# rev02_6.net
KiCad netlist of a schematic drawn in Altium Designer
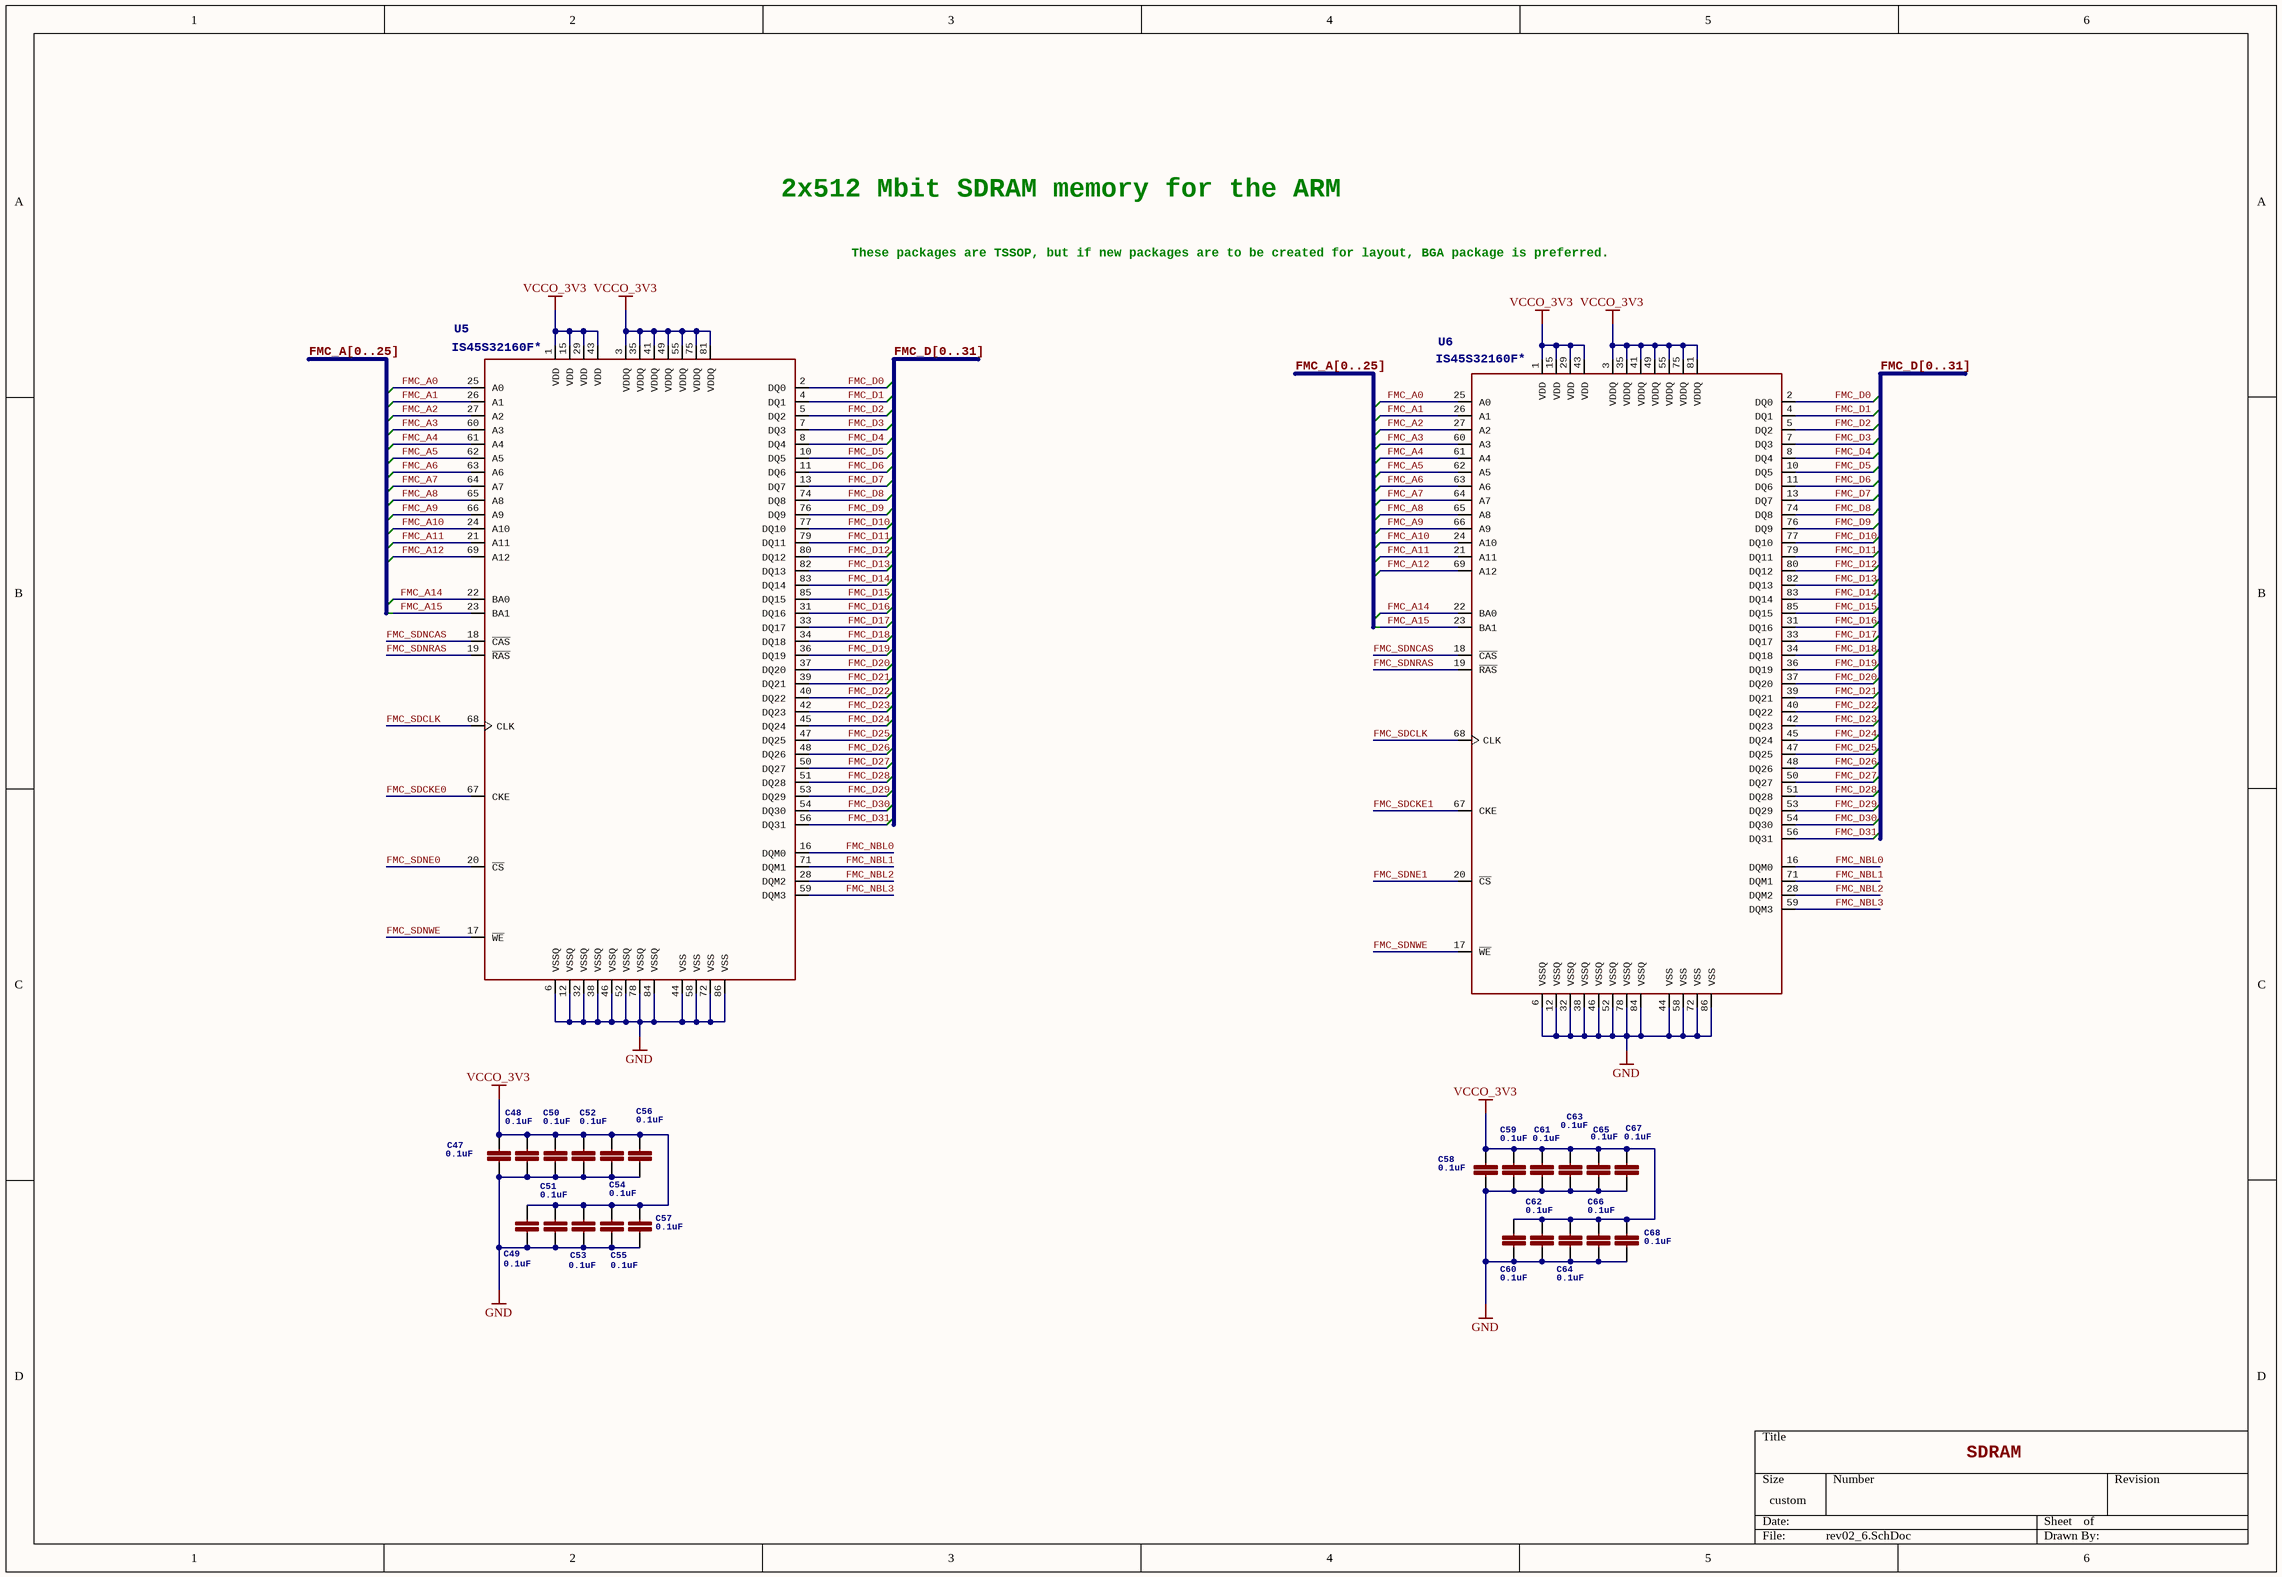
[diagram p0: rev02_6.SchDoc]

(export (version "E")
  (design (tool "Eeschema 10.0.6"))
  (components
    (comp (ref "C47")
      (value "0.1uF")
      (footprint "C_0402")
      (description "0402 CAPACITOR")
      (libsource (lib "resistor") (part "C-EUC0402"))
    )
    (comp (ref "C48")
      (value "0.1uF")
      (footprint "C_0402")
      (description "0402 CAPACITOR")
      (libsource (lib "resistor") (part "C-EUC0402"))
    )
    (comp (ref "C49")
      (value "0.1uF")
      (footprint "C_0402")
      (description "0402 CAPACITOR")
      (libsource (lib "resistor") (part "C-EUC0402"))
    )
    (comp (ref "C50")
      (value "0.1uF")
      (footprint "C_0402")
      (description "0402 CAPACITOR")
      (libsource (lib "resistor") (part "C-EUC0402"))
    )
    (comp (ref "C51")
      (value "0.1uF")
      (footprint "C_0402")
      (description "0402 CAPACITOR")
      (libsource (lib "resistor") (part "C-EUC0402"))
    )
    (comp (ref "C52")
      (value "0.1uF")
      (footprint "C_0402")
      (description "0402 CAPACITOR")
      (libsource (lib "resistor") (part "C-EUC0402"))
    )
    (comp (ref "C53")
      (value "0.1uF")
      (footprint "C_0402")
      (description "0402 CAPACITOR")
      (libsource (lib "resistor") (part "C-EUC0402"))
    )
    (comp (ref "C54")
      (value "0.1uF")
      (footprint "C_0402")
      (description "0402 CAPACITOR")
      (libsource (lib "resistor") (part "C-EUC0402"))
    )
    (comp (ref "C55")
      (value "0.1uF")
      (footprint "C_0402")
      (description "0402 CAPACITOR")
      (libsource (lib "resistor") (part "C-EUC0402"))
    )
    (comp (ref "C56")
      (value "0.1uF")
      (footprint "C_0402")
      (description "0402 CAPACITOR")
      (libsource (lib "resistor") (part "C-EUC0402"))
    )
    (comp (ref "C57")
      (value "0.1uF")
      (footprint "C_0402")
      (description "0402 CAPACITOR")
      (libsource (lib "resistor") (part "C-EUC0402"))
    )
    (comp (ref "C58")
      (value "0.1uF")
      (footprint "C_0402")
      (description "0402 CAPACITOR")
      (libsource (lib "resistor") (part "C-EUC0402"))
    )
    (comp (ref "C59")
      (value "0.1uF")
      (footprint "C_0402")
      (description "0402 CAPACITOR")
      (libsource (lib "resistor") (part "C-EUC0402"))
    )
    (comp (ref "C60")
      (value "0.1uF")
      (footprint "C_0402")
      (description "0402 CAPACITOR")
      (libsource (lib "resistor") (part "C-EUC0402"))
    )
    (comp (ref "C61")
      (value "0.1uF")
      (footprint "C_0402")
      (description "0402 CAPACITOR")
      (libsource (lib "resistor") (part "C-EUC0402"))
    )
    (comp (ref "C62")
      (value "0.1uF")
      (footprint "C_0402")
      (description "0402 CAPACITOR")
      (libsource (lib "resistor") (part "C-EUC0402"))
    )
    (comp (ref "C63")
      (value "0.1uF")
      (footprint "C_0402")
      (description "0402 CAPACITOR")
      (libsource (lib "resistor") (part "C-EUC0402"))
    )
    (comp (ref "C64")
      (value "0.1uF")
      (footprint "C_0402")
      (description "0402 CAPACITOR")
      (libsource (lib "resistor") (part "C-EUC0402"))
    )
    (comp (ref "C65")
      (value "0.1uF")
      (footprint "C_0402")
      (description "0402 CAPACITOR")
      (libsource (lib "resistor") (part "C-EUC0402"))
    )
    (comp (ref "C66")
      (value "0.1uF")
      (footprint "C_0402")
      (description "0402 CAPACITOR")
      (libsource (lib "resistor") (part "C-EUC0402"))
    )
    (comp (ref "C67")
      (value "0.1uF")
      (footprint "C_0402")
      (description "0402 CAPACITOR")
      (libsource (lib "resistor") (part "C-EUC0402"))
    )
    (comp (ref "C68")
      (value "0.1uF")
      (footprint "C_0402")
      (description "0402 CAPACITOR")
      (libsource (lib "resistor") (part "C-EUC0402"))
    )
    (comp (ref "U5")
      (value "IS45S32160F*")
      (footprint "TSSOP50P1180X120-86N")
      (description "16Mx32, 512Mb SDRAM\nClock frequency: 166, 143 MHz")
      (fields (field (name "MPN") "IS45S32160F") (field (name ">NAME") "U5"))
      (libsource (lib "Alpha-IC") (part "IS45S32160F"))
    )
    (comp (ref "U6")
      (value "IS45S32160F*")
      (footprint "TSSOP50P1180X120-86N")
      (description "16Mx32, 512Mb SDRAM\nClock frequency: 166, 143 MHz")
      (fields (field (name "MPN") "IS45S32160F") (field (name ">NAME") "U6"))
      (libsource (lib "Alpha-IC") (part "IS45S32160F"))
    )
  )
  (nets
    (net (code "12") (name "/FMC_A0") (class "Default")
      (node (ref "U5") (pin "25") (pinfunction "A0_25") (pintype "passive"))
      (node (ref "U6") (pin "25") (pinfunction "A0_25") (pintype "passive"))
    )
    (net (code "13") (name "/FMC_A1") (class "Default")
      (node (ref "U5") (pin "26") (pinfunction "A1_26") (pintype "passive"))
      (node (ref "U6") (pin "26") (pinfunction "A1_26") (pintype "passive"))
    )
    (net (code "14") (name "/FMC_A2") (class "Default")
      (node (ref "U5") (pin "27") (pinfunction "A2_27") (pintype "passive"))
      (node (ref "U6") (pin "27") (pinfunction "A2_27") (pintype "passive"))
    )
    (net (code "15") (name "/FMC_A3") (class "Default")
      (node (ref "U5") (pin "60") (pinfunction "A3_60") (pintype "passive"))
      (node (ref "U6") (pin "60") (pinfunction "A3_60") (pintype "passive"))
    )
    (net (code "16") (name "/FMC_A4") (class "Default")
      (node (ref "U5") (pin "61") (pinfunction "A4_61") (pintype "passive"))
      (node (ref "U6") (pin "61") (pinfunction "A4_61") (pintype "passive"))
    )
    (net (code "17") (name "/FMC_A5") (class "Default")
      (node (ref "U5") (pin "62") (pinfunction "A5_62") (pintype "passive"))
      (node (ref "U6") (pin "62") (pinfunction "A5_62") (pintype "passive"))
    )
    (net (code "18") (name "/FMC_A6") (class "Default")
      (node (ref "U5") (pin "63") (pinfunction "A6_63") (pintype "passive"))
      (node (ref "U6") (pin "63") (pinfunction "A6_63") (pintype "passive"))
    )
    (net (code "19") (name "/FMC_A7") (class "Default")
      (node (ref "U5") (pin "64") (pinfunction "A7_64") (pintype "passive"))
      (node (ref "U6") (pin "64") (pinfunction "A7_64") (pintype "passive"))
    )
    (net (code "20") (name "/FMC_A8") (class "Default")
      (node (ref "U5") (pin "65") (pinfunction "A8_65") (pintype "passive"))
      (node (ref "U6") (pin "65") (pinfunction "A8_65") (pintype "passive"))
    )
    (net (code "21") (name "/FMC_A9") (class "Default")
      (node (ref "U5") (pin "66") (pinfunction "A9_66") (pintype "passive"))
      (node (ref "U6") (pin "66") (pinfunction "A9_66") (pintype "passive"))
    )
    (net (code "22") (name "/FMC_A10") (class "Default")
      (node (ref "U5") (pin "24") (pinfunction "A10_24") (pintype "passive"))
      (node (ref "U6") (pin "24") (pinfunction "A10_24") (pintype "passive"))
    )
    (net (code "23") (name "/FMC_A11") (class "Default")
      (node (ref "U5") (pin "21") (pinfunction "A11_21") (pintype "passive"))
      (node (ref "U6") (pin "21") (pinfunction "A11_21") (pintype "passive"))
    )
    (net (code "24") (name "/FMC_A12") (class "Default")
      (node (ref "U5") (pin "69") (pinfunction "A12_69") (pintype "passive"))
      (node (ref "U6") (pin "69") (pinfunction "A12_69") (pintype "passive"))
    )
    (net (code "25") (name "/FMC_A14") (class "Default")
      (node (ref "U5") (pin "22") (pinfunction "BA0_22") (pintype "passive"))
      (node (ref "U6") (pin "22") (pinfunction "BA0_22") (pintype "passive"))
    )
    (net (code "26") (name "/FMC_A15") (class "Default")
      (node (ref "U5") (pin "23") (pinfunction "BA1_23") (pintype "passive"))
      (node (ref "U6") (pin "23") (pinfunction "BA1_23") (pintype "passive"))
    )
    (net (code "28") (name "/FMC_D0") (class "Default")
      (node (ref "U5") (pin "2") (pinfunction "DQ0_2") (pintype "passive"))
      (node (ref "U6") (pin "2") (pinfunction "DQ0_2") (pintype "passive"))
    )
    (net (code "29") (name "/FMC_D1") (class "Default")
      (node (ref "U5") (pin "4") (pinfunction "DQ1_4") (pintype "passive"))
      (node (ref "U6") (pin "4") (pinfunction "DQ1_4") (pintype "passive"))
    )
    (net (code "30") (name "/FMC_D2") (class "Default")
      (node (ref "U5") (pin "5") (pinfunction "DQ2_5") (pintype "passive"))
      (node (ref "U6") (pin "5") (pinfunction "DQ2_5") (pintype "passive"))
    )
    (net (code "31") (name "/FMC_D3") (class "Default")
      (node (ref "U5") (pin "7") (pinfunction "DQ3_7") (pintype "passive"))
      (node (ref "U6") (pin "7") (pinfunction "DQ3_7") (pintype "passive"))
    )
    (net (code "32") (name "/FMC_D4") (class "Default")
      (node (ref "U5") (pin "8") (pinfunction "DQ4_8") (pintype "passive"))
      (node (ref "U6") (pin "8") (pinfunction "DQ4_8") (pintype "passive"))
    )
    (net (code "33") (name "/FMC_D5") (class "Default")
      (node (ref "U5") (pin "10") (pinfunction "DQ5_10") (pintype "passive"))
      (node (ref "U6") (pin "10") (pinfunction "DQ5_10") (pintype "passive"))
    )
    (net (code "34") (name "/FMC_D6") (class "Default")
      (node (ref "U5") (pin "11") (pinfunction "DQ6_11") (pintype "passive"))
      (node (ref "U6") (pin "11") (pinfunction "DQ6_11") (pintype "passive"))
    )
    (net (code "35") (name "/FMC_D7") (class "Default")
      (node (ref "U5") (pin "13") (pinfunction "DQ7_13") (pintype "passive"))
      (node (ref "U6") (pin "13") (pinfunction "DQ7_13") (pintype "passive"))
    )
    (net (code "36") (name "/FMC_D8") (class "Default")
      (node (ref "U5") (pin "74") (pinfunction "DQ8_74") (pintype "passive"))
      (node (ref "U6") (pin "74") (pinfunction "DQ8_74") (pintype "passive"))
    )
    (net (code "37") (name "/FMC_D9") (class "Default")
      (node (ref "U5") (pin "76") (pinfunction "DQ9_76") (pintype "passive"))
      (node (ref "U6") (pin "76") (pinfunction "DQ9_76") (pintype "passive"))
    )
    (net (code "38") (name "/FMC_D10") (class "Default")
      (node (ref "U5") (pin "77") (pinfunction "DQ10_77") (pintype "passive"))
      (node (ref "U6") (pin "77") (pinfunction "DQ10_77") (pintype "passive"))
    )
    (net (code "39") (name "/FMC_D11") (class "Default")
      (node (ref "U5") (pin "79") (pinfunction "DQ11_79") (pintype "passive"))
      (node (ref "U6") (pin "79") (pinfunction "DQ11_79") (pintype "passive"))
    )
    (net (code "40") (name "/FMC_D12") (class "Default")
      (node (ref "U5") (pin "80") (pinfunction "DQ12_80") (pintype "passive"))
      (node (ref "U6") (pin "80") (pinfunction "DQ12_80") (pintype "passive"))
    )
    (net (code "41") (name "/FMC_D13") (class "Default")
      (node (ref "U5") (pin "82") (pinfunction "DQ13_82") (pintype "passive"))
      (node (ref "U6") (pin "82") (pinfunction "DQ13_82") (pintype "passive"))
    )
    (net (code "42") (name "/FMC_D14") (class "Default")
      (node (ref "U5") (pin "83") (pinfunction "DQ14_83") (pintype "passive"))
      (node (ref "U6") (pin "83") (pinfunction "DQ14_83") (pintype "passive"))
    )
    (net (code "43") (name "/FMC_D15") (class "Default")
      (node (ref "U5") (pin "85") (pinfunction "DQ15_85") (pintype "passive"))
      (node (ref "U6") (pin "85") (pinfunction "DQ15_85") (pintype "passive"))
    )
    (net (code "44") (name "/FMC_D16") (class "Default")
      (node (ref "U5") (pin "31") (pinfunction "DQ16_31") (pintype "passive"))
      (node (ref "U6") (pin "31") (pinfunction "DQ16_31") (pintype "passive"))
    )
    (net (code "45") (name "/FMC_D17") (class "Default")
      (node (ref "U5") (pin "33") (pinfunction "DQ17_33") (pintype "passive"))
      (node (ref "U6") (pin "33") (pinfunction "DQ17_33") (pintype "passive"))
    )
    (net (code "46") (name "/FMC_D18") (class "Default")
      (node (ref "U5") (pin "34") (pinfunction "DQ18_34") (pintype "passive"))
      (node (ref "U6") (pin "34") (pinfunction "DQ18_34") (pintype "passive"))
    )
    (net (code "47") (name "/FMC_D19") (class "Default")
      (node (ref "U5") (pin "36") (pinfunction "DQ19_36") (pintype "passive"))
      (node (ref "U6") (pin "36") (pinfunction "DQ19_36") (pintype "passive"))
    )
    (net (code "48") (name "/FMC_D20") (class "Default")
      (node (ref "U5") (pin "37") (pinfunction "DQ20_37") (pintype "passive"))
      (node (ref "U6") (pin "37") (pinfunction "DQ20_37") (pintype "passive"))
    )
    (net (code "49") (name "/FMC_D21") (class "Default")
      (node (ref "U5") (pin "39") (pinfunction "DQ21_39") (pintype "passive"))
      (node (ref "U6") (pin "39") (pinfunction "DQ21_39") (pintype "passive"))
    )
    (net (code "50") (name "/FMC_D22") (class "Default")
      (node (ref "U5") (pin "40") (pinfunction "DQ22_40") (pintype "passive"))
      (node (ref "U6") (pin "40") (pinfunction "DQ22_40") (pintype "passive"))
    )
    (net (code "51") (name "/FMC_D23") (class "Default")
      (node (ref "U5") (pin "42") (pinfunction "DQ23_42") (pintype "passive"))
      (node (ref "U6") (pin "42") (pinfunction "DQ23_42") (pintype "passive"))
    )
    (net (code "52") (name "/FMC_D24") (class "Default")
      (node (ref "U5") (pin "45") (pinfunction "DQ24_45") (pintype "passive"))
      (node (ref "U6") (pin "45") (pinfunction "DQ24_45") (pintype "passive"))
    )
    (net (code "53") (name "/FMC_D25") (class "Default")
      (node (ref "U5") (pin "47") (pinfunction "DQ25_47") (pintype "passive"))
      (node (ref "U6") (pin "47") (pinfunction "DQ25_47") (pintype "passive"))
    )
    (net (code "54") (name "/FMC_D26") (class "Default")
      (node (ref "U5") (pin "48") (pinfunction "DQ26_48") (pintype "passive"))
      (node (ref "U6") (pin "48") (pinfunction "DQ26_48") (pintype "passive"))
    )
    (net (code "55") (name "/FMC_D27") (class "Default")
      (node (ref "U5") (pin "50") (pinfunction "DQ27_50") (pintype "passive"))
      (node (ref "U6") (pin "50") (pinfunction "DQ27_50") (pintype "passive"))
    )
    (net (code "56") (name "/FMC_D28") (class "Default")
      (node (ref "U5") (pin "51") (pinfunction "DQ28_51") (pintype "passive"))
      (node (ref "U6") (pin "51") (pinfunction "DQ28_51") (pintype "passive"))
    )
    (net (code "57") (name "/FMC_D29") (class "Default")
      (node (ref "U5") (pin "53") (pinfunction "DQ29_53") (pintype "passive"))
      (node (ref "U6") (pin "53") (pinfunction "DQ29_53") (pintype "passive"))
    )
    (net (code "58") (name "/FMC_D30") (class "Default")
      (node (ref "U5") (pin "54") (pinfunction "DQ30_54") (pintype "passive"))
      (node (ref "U6") (pin "54") (pinfunction "DQ30_54") (pintype "passive"))
    )
    (net (code "59") (name "/FMC_D31") (class "Default")
      (node (ref "U5") (pin "56") (pinfunction "DQ31_56") (pintype "passive"))
      (node (ref "U6") (pin "56") (pinfunction "DQ31_56") (pintype "passive"))
    )
    (net (code "61") (name "/FMC_NBL0") (class "Default")
      (node (ref "U5") (pin "16") (pinfunction "DQM0_16") (pintype "passive"))
      (node (ref "U6") (pin "16") (pinfunction "DQM0_16") (pintype "passive"))
    )
    (net (code "62") (name "/FMC_NBL1") (class "Default")
      (node (ref "U5") (pin "71") (pinfunction "DQM1_71") (pintype "passive"))
      (node (ref "U6") (pin "71") (pinfunction "DQM1_71") (pintype "passive"))
    )
    (net (code "63") (name "/FMC_NBL2") (class "Default")
      (node (ref "U5") (pin "28") (pinfunction "DQM2_28") (pintype "passive"))
      (node (ref "U6") (pin "28") (pinfunction "DQM2_28") (pintype "passive"))
    )
    (net (code "64") (name "/FMC_NBL3") (class "Default")
      (node (ref "U5") (pin "59") (pinfunction "DQM3_59") (pintype "passive"))
      (node (ref "U6") (pin "59") (pinfunction "DQM3_59") (pintype "passive"))
    )
    (net (code "65") (name "/FMC_SDCKE0") (class "Default")
      (node (ref "U5") (pin "67") (pinfunction "CKE_67") (pintype "passive"))
    )
    (net (code "66") (name "/FMC_SDCKE1") (class "Default")
      (node (ref "U6") (pin "67") (pinfunction "CKE_67") (pintype "passive"))
    )
    (net (code "67") (name "/FMC_SDCLK") (class "Default")
      (node (ref "U5") (pin "68") (pinfunction "CLK_68") (pintype "passive"))
      (node (ref "U6") (pin "68") (pinfunction "CLK_68") (pintype "passive"))
    )
    (net (code "68") (name "/FMC_SDNCAS") (class "Default")
      (node (ref "U5") (pin "18") (pinfunction "~{CAS}_18") (pintype "passive"))
      (node (ref "U6") (pin "18") (pinfunction "~{CAS}_18") (pintype "passive"))
    )
    (net (code "69") (name "/FMC_SDNE0") (class "Default")
      (node (ref "U5") (pin "20") (pinfunction "~{CS}_20") (pintype "passive"))
    )
    (net (code "70") (name "/FMC_SDNE1") (class "Default")
      (node (ref "U6") (pin "20") (pinfunction "~{CS}_20") (pintype "passive"))
    )
    (net (code "71") (name "/FMC_SDNRAS") (class "Default")
      (node (ref "U5") (pin "19") (pinfunction "~{RAS}_19") (pintype "passive"))
      (node (ref "U6") (pin "19") (pinfunction "~{RAS}_19") (pintype "passive"))
    )
    (net (code "72") (name "/FMC_SDNWE") (class "Default")
      (node (ref "U5") (pin "17") (pinfunction "~{WE}_17") (pintype "passive"))
      (node (ref "U6") (pin "17") (pinfunction "~{WE}_17") (pintype "passive"))
    )
    (net (code "73") (name "GND") (class "Default")
      (node (ref "C47") (pin "2") (pinfunction "2_2") (pintype "passive"))
      (node (ref "C48") (pin "2") (pinfunction "2_2") (pintype "passive"))
      (node (ref "C49") (pin "2") (pinfunction "2_2") (pintype "passive"))
      (node (ref "C50") (pin "2") (pinfunction "2_2") (pintype "passive"))
      (node (ref "C51") (pin "2") (pinfunction "2_2") (pintype "passive"))
      (node (ref "C52") (pin "2") (pinfunction "2_2") (pintype "passive"))
      (node (ref "C53") (pin "2") (pinfunction "2_2") (pintype "passive"))
      (node (ref "C54") (pin "2") (pinfunction "2_2") (pintype "passive"))
      (node (ref "C55") (pin "2") (pinfunction "2_2") (pintype "passive"))
      (node (ref "C56") (pin "2") (pinfunction "2_2") (pintype "passive"))
      (node (ref "C57") (pin "2") (pinfunction "2_2") (pintype "passive"))
      (node (ref "C58") (pin "2") (pinfunction "2_2") (pintype "passive"))
      (node (ref "C59") (pin "2") (pinfunction "2_2") (pintype "passive"))
      (node (ref "C60") (pin "2") (pinfunction "2_2") (pintype "passive"))
      (node (ref "C61") (pin "2") (pinfunction "2_2") (pintype "passive"))
      (node (ref "C62") (pin "2") (pinfunction "2_2") (pintype "passive"))
      (node (ref "C63") (pin "2") (pinfunction "2_2") (pintype "passive"))
      (node (ref "C64") (pin "2") (pinfunction "2_2") (pintype "passive"))
      (node (ref "C65") (pin "2") (pinfunction "2_2") (pintype "passive"))
      (node (ref "C66") (pin "2") (pinfunction "2_2") (pintype "passive"))
      (node (ref "C67") (pin "2") (pinfunction "2_2") (pintype "passive"))
      (node (ref "C68") (pin "2") (pinfunction "2_2") (pintype "passive"))
      (node (ref "U5") (pin "12") (pinfunction "VSSQ_12") (pintype "power_in"))
      (node (ref "U5") (pin "32") (pinfunction "VSSQ_32") (pintype "power_in"))
      (node (ref "U5") (pin "38") (pinfunction "VSSQ_38") (pintype "power_in"))
      (node (ref "U5") (pin "44") (pinfunction "VSS_44") (pintype "power_in"))
      (node (ref "U5") (pin "46") (pinfunction "VSSQ_46") (pintype "power_in"))
      (node (ref "U5") (pin "52") (pinfunction "VSSQ_52") (pintype "power_in"))
      (node (ref "U5") (pin "58") (pinfunction "VSS_58") (pintype "power_in"))
      (node (ref "U5") (pin "6") (pinfunction "VSSQ_6") (pintype "power_in"))
      (node (ref "U5") (pin "72") (pinfunction "VSS_72") (pintype "power_in"))
      (node (ref "U5") (pin "78") (pinfunction "VSSQ_78") (pintype "power_in"))
      (node (ref "U5") (pin "84") (pinfunction "VSSQ_84") (pintype "power_in"))
      (node (ref "U5") (pin "86") (pinfunction "VSS_86") (pintype "power_in"))
      (node (ref "U6") (pin "12") (pinfunction "VSSQ_12") (pintype "power_in"))
      (node (ref "U6") (pin "32") (pinfunction "VSSQ_32") (pintype "power_in"))
      (node (ref "U6") (pin "38") (pinfunction "VSSQ_38") (pintype "power_in"))
      (node (ref "U6") (pin "44") (pinfunction "VSS_44") (pintype "power_in"))
      (node (ref "U6") (pin "46") (pinfunction "VSSQ_46") (pintype "power_in"))
      (node (ref "U6") (pin "52") (pinfunction "VSSQ_52") (pintype "power_in"))
      (node (ref "U6") (pin "58") (pinfunction "VSS_58") (pintype "power_in"))
      (node (ref "U6") (pin "6") (pinfunction "VSSQ_6") (pintype "power_in"))
      (node (ref "U6") (pin "72") (pinfunction "VSS_72") (pintype "power_in"))
      (node (ref "U6") (pin "78") (pinfunction "VSSQ_78") (pintype "power_in"))
      (node (ref "U6") (pin "84") (pinfunction "VSSQ_84") (pintype "power_in"))
      (node (ref "U6") (pin "86") (pinfunction "VSS_86") (pintype "power_in"))
    )
    (net (code "74") (name "VCCO_3V3") (class "Default")
      (node (ref "C47") (pin "1") (pinfunction "1_1") (pintype "passive"))
      (node (ref "C48") (pin "1") (pinfunction "1_1") (pintype "passive"))
      (node (ref "C49") (pin "1") (pinfunction "1_1") (pintype "passive"))
      (node (ref "C50") (pin "1") (pinfunction "1_1") (pintype "passive"))
      (node (ref "C51") (pin "1") (pinfunction "1_1") (pintype "passive"))
      (node (ref "C52") (pin "1") (pinfunction "1_1") (pintype "passive"))
      (node (ref "C53") (pin "1") (pinfunction "1_1") (pintype "passive"))
      (node (ref "C54") (pin "1") (pinfunction "1_1") (pintype "passive"))
      (node (ref "C55") (pin "1") (pinfunction "1_1") (pintype "passive"))
      (node (ref "C56") (pin "1") (pinfunction "1_1") (pintype "passive"))
      (node (ref "C57") (pin "1") (pinfunction "1_1") (pintype "passive"))
      (node (ref "C58") (pin "1") (pinfunction "1_1") (pintype "passive"))
      (node (ref "C59") (pin "1") (pinfunction "1_1") (pintype "passive"))
      (node (ref "C60") (pin "1") (pinfunction "1_1") (pintype "passive"))
      (node (ref "C61") (pin "1") (pinfunction "1_1") (pintype "passive"))
      (node (ref "C62") (pin "1") (pinfunction "1_1") (pintype "passive"))
      (node (ref "C63") (pin "1") (pinfunction "1_1") (pintype "passive"))
      (node (ref "C64") (pin "1") (pinfunction "1_1") (pintype "passive"))
      (node (ref "C65") (pin "1") (pinfunction "1_1") (pintype "passive"))
      (node (ref "C66") (pin "1") (pinfunction "1_1") (pintype "passive"))
      (node (ref "C67") (pin "1") (pinfunction "1_1") (pintype "passive"))
      (node (ref "C68") (pin "1") (pinfunction "1_1") (pintype "passive"))
      (node (ref "U5") (pin "1") (pinfunction "VDD_1") (pintype "power_in"))
      (node (ref "U5") (pin "15") (pinfunction "VDD_15") (pintype "power_in"))
      (node (ref "U5") (pin "29") (pinfunction "VDD_29") (pintype "power_in"))
      (node (ref "U5") (pin "3") (pinfunction "VDDQ_3") (pintype "power_in"))
      (node (ref "U5") (pin "35") (pinfunction "VDDQ_35") (pintype "power_in"))
      (node (ref "U5") (pin "41") (pinfunction "VDDQ_41") (pintype "power_in"))
      (node (ref "U5") (pin "43") (pinfunction "VDD_43") (pintype "power_in"))
      (node (ref "U5") (pin "49") (pinfunction "VDDQ_49") (pintype "power_in"))
      (node (ref "U5") (pin "55") (pinfunction "VDDQ_55") (pintype "power_in"))
      (node (ref "U5") (pin "75") (pinfunction "VDDQ_75") (pintype "power_in"))
      (node (ref "U5") (pin "81") (pinfunction "VDDQ_81") (pintype "power_in"))
      (node (ref "U6") (pin "1") (pinfunction "VDD_1") (pintype "power_in"))
      (node (ref "U6") (pin "15") (pinfunction "VDD_15") (pintype "power_in"))
      (node (ref "U6") (pin "29") (pinfunction "VDD_29") (pintype "power_in"))
      (node (ref "U6") (pin "3") (pinfunction "VDDQ_3") (pintype "power_in"))
      (node (ref "U6") (pin "35") (pinfunction "VDDQ_35") (pintype "power_in"))
      (node (ref "U6") (pin "41") (pinfunction "VDDQ_41") (pintype "power_in"))
      (node (ref "U6") (pin "43") (pinfunction "VDD_43") (pintype "power_in"))
      (node (ref "U6") (pin "49") (pinfunction "VDDQ_49") (pintype "power_in"))
      (node (ref "U6") (pin "55") (pinfunction "VDDQ_55") (pintype "power_in"))
      (node (ref "U6") (pin "75") (pinfunction "VDDQ_75") (pintype "power_in"))
      (node (ref "U6") (pin "81") (pinfunction "VDDQ_81") (pintype "power_in"))
    )
  )
)
